# SH1_-_POWER.net
KiCad netlist of a schematic drawn in Altium Designer
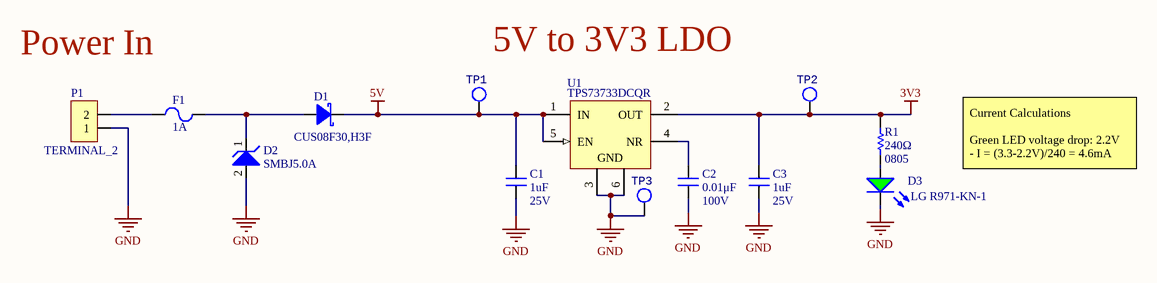
[diagram p0: SH1 - POWER.SchDoc]

(export (version "E")
  (design (tool "Eeschema 10.0.6"))
  (components
    (comp (ref "C1")
      (value "~")
      (footprint "CAPC2012X140N")
      (description "CAP CER 1UF 25V X7R 0805")
      (fields
        (field (name "TOLERANCE") "10%")
        (field (name "CAPACITANCE") "1uF")
        (field (name "VOLTAGE RATING (DC)") "25V")
      )
      (libsource (lib "*") (part "CAP_1uF_25V_0805"))
    )
    (comp (ref "C2")
      (value "0.01μF")
      (footprint "CAP2012")
      (description "CAP CER 10000PF 100V X7R 0805")
      (fields
        (field (name "TOLERANCE") "10%")
        (field (name "VOLTAGE RATING") "100V")
        (field (name "Comment") "CAP_0.01uF_100V_0805")
      )
      (libsource (lib "UWRT_Schematic_Library_2020") (part "CAP_0.01uF_100V_0805"))
    )
    (comp (ref "C3")
      (value "~")
      (footprint "CAPC2012X140N")
      (description "CAP CER 1UF 25V X7R 0805")
      (fields
        (field (name "TOLERANCE") "10%")
        (field (name "CAPACITANCE") "1uF")
        (field (name "VOLTAGE RATING (DC)") "25V")
      )
      (libsource (lib "*") (part "CAP_1uF_25V_0805"))
    )
    (comp (ref "D1")
      (value "DIO_SCHOTTKY_30V_800mA")
      (footprint "SOD-323_UNIDIR")
      (description "DIODE SCHOTTKY 30V 800MA USC")
      (fields (field (name "MANUFACTURER PART NUMBER 1") "CUS08F30,H3F"))
      (libsource (lib "UWRT_Schematic_Library_2020") (part "DIO_SCHOTTKY_30V_800mA"))
    )
    (comp (ref "D2")
      (value "TVS_DIODE_UNIDIR_5V")
      (footprint "SMBJ5.0A")
      (description "TVS DIODE 5V 9.2V DO214AA")
      (fields (field (name "MANUFACTURER PART NUMBER 1") "SMBJ5.0A"))
      (libsource (lib "UWRT_Schematic_Library_2020") (part "TVS_DIODE_UNIDIR_5V"))
    )
    (comp (ref "D3")
      (value "LG R971-KN-1")
      (footprint "LED_0805_LINE")
      (description "LED GREEN DIFFUSED 0805 SMD")
      (libsource (lib "UWRT_Schematic_Library_2020") (part "DIO_LED_G"))
    )
    (comp (ref "F1")
      (value "FUSE_1A_1206")
      (footprint "FUSC3215X78N")
      (description "FUSE BOARD MOUNT 1A 125VAC 63VDC")
      (fields (field (name "CURRENT RATING") "1A"))
      (libsource (lib "UWRT_Schematic_Library_2020") (part "FUSE_1A_1206"))
    )
    (comp (ref "P1")
      (value "TERMINAL_2")
      (footprint "OSTYK51102030")
      (description "Header, 2-Pin")
      (libsource (lib "UWRT_Schematic_Library_2020") (part "TERMINAL_2"))
    )
    (comp (ref "R1")
      (value "240")
      (footprint "RESC2012X60N")
      (description "RES 240 OHM 1% 1/8W 0805")
      (fields
        (field (name "TOLERANCE") "1%")
        (field (name "RESISTANCE") "240Ω")
        (field (name "CASE CODE (IMPERIAL)") "0805")
      )
      (libsource (lib "UWRT_Schematic_Library_2020") (part "RES_240Ω_0805_1%"))
    )
    (comp (ref "TP1")
      (value "TESTPOINT_LOOP")
      (footprint "TESTPOINT_LOOP")
      (description "Loop testpoint through-hole pad")
      (libsource (lib "UWRT_Schematic_Library_2020") (part "TESTPOINT_LOOP"))
    )
    (comp (ref "TP2")
      (value "TESTPOINT_LOOP")
      (footprint "TESTPOINT_LOOP")
      (description "Loop testpoint through-hole pad")
      (libsource (lib "UWRT_Schematic_Library_2020") (part "TESTPOINT_LOOP"))
    )
    (comp (ref "TP3")
      (value "TESTPOINT_LOOP")
      (footprint "TESTPOINT_LOOP")
      (description "Loop testpoint through-hole pad")
      (libsource (lib "UWRT_Schematic_Library_2020") (part "TESTPOINT_LOOP"))
    )
    (comp (ref "U1")
      (value "TPS73733DCQR")
      (footprint "UWRT_Footprint_Library_2020:SOT-223-6")
      (description "IC REG LINEAR 3.3V 1A SOT223-6")
      (fields (field (name "MANUFACTURER") "Texas Instruments"))
      (libsource (lib "Altium Content Vault") (part "LDO_3.3V_1A"))
    )
  )
  (nets
    (net (code "1") (name "3V3") (class "Default")
      (node (ref "C3") (pin "2") (pinfunction "2_2") (pintype "passive"))
      (node (ref "R1") (pin "2") (pinfunction "2_2") (pintype "passive"))
      (node (ref "TP2") (pin "1") (pintype "passive"))
      (node (ref "U1") (pin "2") (pinfunction "OUT_2") (pintype "power_in"))
    )
    (net (code "2") (name "5V") (class "Default")
      (node (ref "C1") (pin "1") (pinfunction "1_1") (pintype "passive"))
      (node (ref "D1") (pin "2") (pinfunction "Cathode_2") (pintype "passive"))
      (node (ref "TP1") (pin "1") (pintype "passive"))
      (node (ref "U1") (pin "1") (pinfunction "IN_1") (pintype "power_in"))
      (node (ref "U1") (pin "5") (pinfunction "EN_5") (pintype "input"))
    )
    (net (code "3") (name "GND") (class "Default")
      (node (ref "C1") (pin "2") (pinfunction "2_2") (pintype "passive"))
      (node (ref "C2") (pin "1") (pinfunction "1_1") (pintype "passive"))
      (node (ref "C3") (pin "1") (pinfunction "1_1") (pintype "passive"))
      (node (ref "D2") (pin "2") (pinfunction "2_2") (pintype "passive"))
      (node (ref "D3") (pin "2") (pinfunction "K_2") (pintype "passive"))
      (node (ref "P1") (pin "1") (pinfunction "1_1") (pintype "passive"))
      (node (ref "TP3") (pin "1") (pintype "passive"))
      (node (ref "U1") (pin "3") (pinfunction "GND_3") (pintype "power_in"))
      (node (ref "U1") (pin "6") (pinfunction "GND_6") (pintype "power_in"))
    )
    (net (code "4") (name "Net-(D1-Anode)") (class "Default")
      (node (ref "D1") (pin "1") (pinfunction "Anode_1") (pintype "passive"))
      (node (ref "D2") (pin "1") (pinfunction "1_1") (pintype "passive"))
      (node (ref "F1") (pin "2") (pinfunction "2_2") (pintype "passive"))
    )
    (net (code "5") (name "Net-(D3-A)") (class "Default")
      (node (ref "D3") (pin "1") (pinfunction "A_1") (pintype "passive"))
      (node (ref "R1") (pin "1") (pinfunction "1_1") (pintype "passive"))
    )
    (net (code "6") (name "Net-(F1-Pad1)") (class "Default")
      (node (ref "F1") (pin "1") (pinfunction "1_1") (pintype "passive"))
      (node (ref "P1") (pin "2") (pinfunction "2_2") (pintype "passive"))
    )
    (net (code "7") (name "Net-(U1-NR)") (class "Default")
      (node (ref "C2") (pin "2") (pinfunction "2_2") (pintype "passive"))
      (node (ref "U1") (pin "4") (pinfunction "NR_4") (pintype "passive"))
    )
  )
)
